# G208B.net
KiCad netlist of a schematic drawn in EAGLE
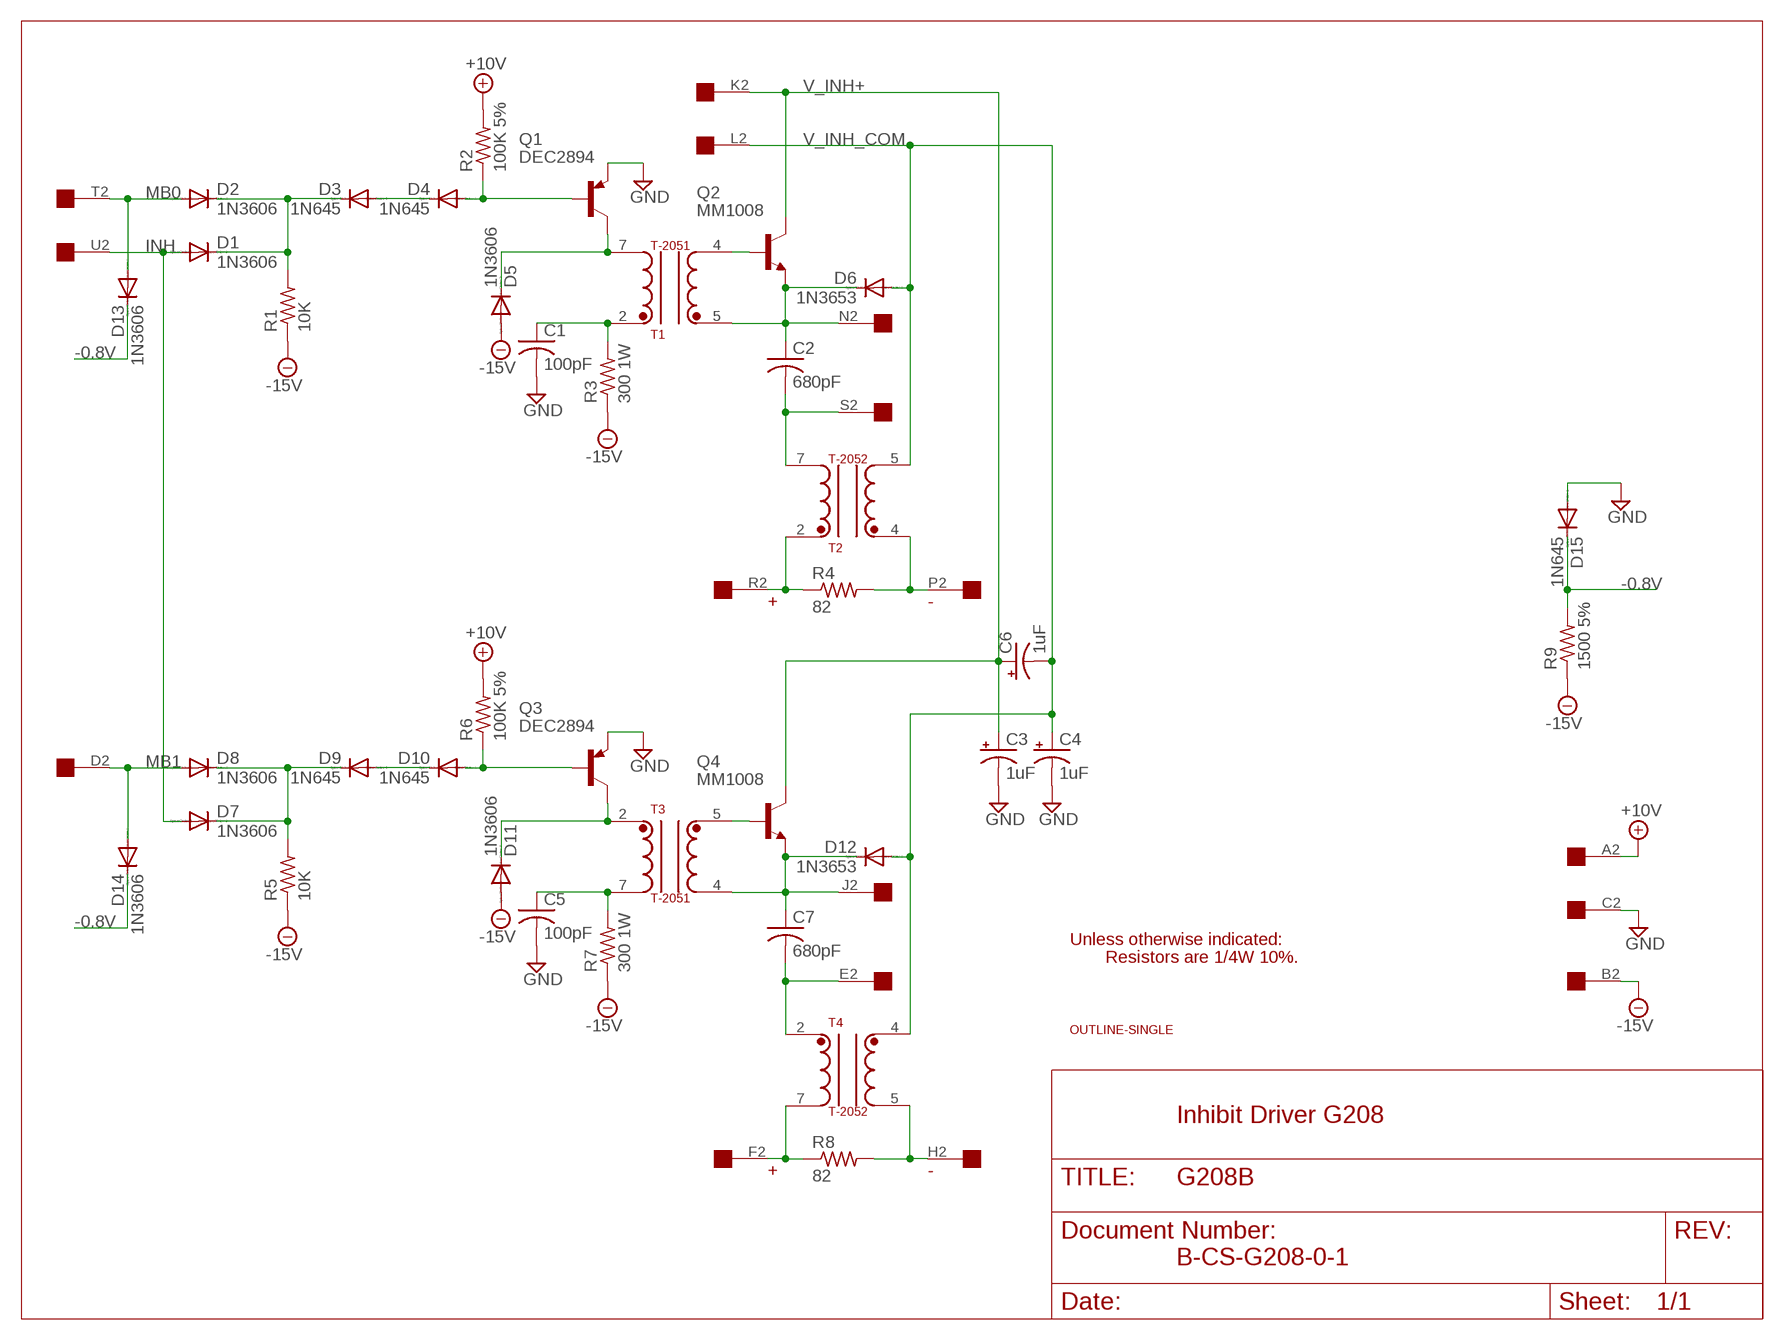
[diagram p0: schematic, sheet 1]

(export (version "E")
  (design (tool "Eeschema 10.0.6"))
  (components
    (comp (ref "C1")
      (value "100pF")
      (footprint "eagle-import:C075-032X103")
      (libsource (lib "eagle-import") (part "C-US075-032X103"))
    )
    (comp (ref "C2")
      (value "680pF")
      (footprint "eagle-import:C075-032X103")
      (libsource (lib "eagle-import") (part "C-US075-032X103"))
    )
    (comp (ref "C3")
      (value "1uF")
      (footprint "eagle-import:E25-9")
      (libsource (lib "eagle-import") (part "CPOL-USE25-9AXIAL"))
    )
    (comp (ref "C4")
      (value "1uF")
      (footprint "eagle-import:E25-9")
      (libsource (lib "eagle-import") (part "CPOL-USE25-9AXIAL"))
    )
    (comp (ref "C5")
      (value "100pF")
      (footprint "eagle-import:C075-032X103")
      (libsource (lib "eagle-import") (part "C-US075-032X103"))
    )
    (comp (ref "C6")
      (value "1uF")
      (footprint "eagle-import:E25-9")
      (libsource (lib "eagle-import") (part "CPOL-USE25-9AXIAL"))
    )
    (comp (ref "C7")
      (value "680pF")
      (footprint "eagle-import:C075-032X103")
      (libsource (lib "eagle-import") (part "C-US075-032X103"))
    )
    (comp (ref "D1")
      (value "1N3606")
      (footprint "eagle-import:DO35-10")
      (libsource (lib "eagle-import") (part "1N4148DO35-10"))
    )
    (comp (ref "D2")
      (value "1N3606")
      (footprint "eagle-import:DO35-10")
      (libsource (lib "eagle-import") (part "1N4148DO35-10"))
    )
    (comp (ref "D3")
      (value "1N645")
      (footprint "eagle-import:DO35-10")
      (libsource (lib "eagle-import") (part "1N4148DO35-10"))
    )
    (comp (ref "D4")
      (value "1N645")
      (footprint "eagle-import:DO35-10")
      (libsource (lib "eagle-import") (part "1N4148DO35-10"))
    )
    (comp (ref "D5")
      (value "1N3606")
      (footprint "eagle-import:DO35-10")
      (libsource (lib "eagle-import") (part "1N4148DO35-10"))
    )
    (comp (ref "D6")
      (value "1N3653")
      (footprint "eagle-import:DO35-10")
      (libsource (lib "eagle-import") (part "1N4148DO35-10"))
    )
    (comp (ref "D7")
      (value "1N3606")
      (footprint "eagle-import:DO35-10")
      (libsource (lib "eagle-import") (part "1N4148DO35-10"))
    )
    (comp (ref "D8")
      (value "1N3606")
      (footprint "eagle-import:DO35-10")
      (libsource (lib "eagle-import") (part "1N4148DO35-10"))
    )
    (comp (ref "D9")
      (value "1N645")
      (footprint "eagle-import:DO35-10")
      (libsource (lib "eagle-import") (part "1N4148DO35-10"))
    )
    (comp (ref "D10")
      (value "1N645")
      (footprint "eagle-import:DO35-10")
      (libsource (lib "eagle-import") (part "1N4148DO35-10"))
    )
    (comp (ref "D11")
      (value "1N3606")
      (footprint "eagle-import:DO35-10")
      (libsource (lib "eagle-import") (part "1N4148DO35-10"))
    )
    (comp (ref "D12")
      (value "1N3653")
      (footprint "eagle-import:DO35-10")
      (libsource (lib "eagle-import") (part "1N4148DO35-10"))
    )
    (comp (ref "D13")
      (value "1N3606")
      (footprint "eagle-import:DO35-10")
      (libsource (lib "eagle-import") (part "1N4148DO35-10"))
    )
    (comp (ref "D14")
      (value "1N3606")
      (footprint "eagle-import:DO35-10")
      (libsource (lib "eagle-import") (part "1N4148DO35-10"))
    )
    (comp (ref "D15")
      (value "1N645")
      (footprint "eagle-import:DO35-10")
      (libsource (lib "eagle-import") (part "1N4148DO35-10"))
    )
    (comp (ref "Q1")
      (value "DEC2894")
      (footprint "eagle-import:TO39")
      (libsource (lib "eagle-import") (part "2N2904"))
    )
    (comp (ref "Q2")
      (value "MM1008")
      (footprint "eagle-import:TO5")
      (libsource (lib "eagle-import") (part "2N2102"))
    )
    (comp (ref "Q3")
      (value "DEC2894")
      (footprint "eagle-import:TO39")
      (libsource (lib "eagle-import") (part "2N2904"))
    )
    (comp (ref "Q4")
      (value "MM1008")
      (footprint "eagle-import:TO5")
      (libsource (lib "eagle-import") (part "2N2102"))
    )
    (comp (ref "R1")
      (value "10K")
      (footprint "eagle-import:0207_10")
      (libsource (lib "eagle-import") (part "R-US_0207/10"))
    )
    (comp (ref "R2")
      (value "100K 5%")
      (footprint "eagle-import:0207_10")
      (libsource (lib "eagle-import") (part "R-US_0207/10"))
    )
    (comp (ref "R3")
      (value "300 1W")
      (footprint "eagle-import:0617_22")
      (libsource (lib "eagle-import") (part "R-US_0617/22"))
    )
    (comp (ref "R4")
      (value "82")
      (footprint "eagle-import:0207_10")
      (libsource (lib "eagle-import") (part "R-US_0207/10"))
    )
    (comp (ref "R5")
      (value "10K")
      (footprint "eagle-import:0207_10")
      (libsource (lib "eagle-import") (part "R-US_0207/10"))
    )
    (comp (ref "R6")
      (value "100K 5%")
      (footprint "eagle-import:0207_10")
      (libsource (lib "eagle-import") (part "R-US_0207/10"))
    )
    (comp (ref "R7")
      (value "300 1W")
      (footprint "eagle-import:0617_22")
      (libsource (lib "eagle-import") (part "R-US_0617/22"))
    )
    (comp (ref "R8")
      (value "82")
      (footprint "eagle-import:0207_10")
      (libsource (lib "eagle-import") (part "R-US_0207/10"))
    )
    (comp (ref "R9")
      (value "1500 5%")
      (footprint "eagle-import:0207_10")
      (libsource (lib "eagle-import") (part "R-US_0207/10"))
    )
    (comp (ref "T1")
      (value "T-2051")
      (footprint "eagle-import:TRANSFORMER")
      (libsource (lib "eagle-import") (part "T-2051"))
    )
    (comp (ref "T2")
      (value "T-2052")
      (footprint "eagle-import:TRANSFORMER")
      (libsource (lib "eagle-import") (part "T-2052"))
    )
    (comp (ref "T3")
      (value "T-2051")
      (footprint "eagle-import:TRANSFORMER")
      (libsource (lib "eagle-import") (part "T-2051"))
    )
    (comp (ref "T4")
      (value "T-2052")
      (footprint "eagle-import:TRANSFORMER")
      (libsource (lib "eagle-import") (part "T-2052"))
    )
    (comp (ref "U$1")
      (value "OUTLINE-SINGLE")
      (footprint "eagle-import:SINGLE")
      (libsource (lib "eagle-import") (part "OUTLINE-SINGLE"))
    )
    (comp (ref "U$2")
      (value "EDGE-1")
      (footprint "eagle-import:EDGE-CON1")
      (libsource (lib "eagle-import") (part "EDGE-1"))
    )
  )
  (nets
    (net (code "1") (name "+10V") (class "Default")
      (node (ref "R2") (pin "2") (pinfunction "2_2") (pintype "passive"))
      (node (ref "R6") (pin "2") (pinfunction "2_2") (pintype "passive"))
      (node (ref "U$2") (pin "A2") (pinfunction "1_A2") (pintype "bidirectional"))
    )
    (net (code "2") (name "-15V") (class "Default")
      (node (ref "D11") (pin "A") (pinfunction "A_A") (pintype "passive"))
      (node (ref "D5") (pin "A") (pinfunction "A_A") (pintype "passive"))
      (node (ref "R1") (pin "1") (pinfunction "1_1") (pintype "passive"))
      (node (ref "R3") (pin "1") (pinfunction "1_1") (pintype "passive"))
      (node (ref "R5") (pin "1") (pinfunction "1_1") (pintype "passive"))
      (node (ref "R7") (pin "1") (pinfunction "1_1") (pintype "passive"))
      (node (ref "R9") (pin "1") (pinfunction "1_1") (pintype "passive"))
      (node (ref "U$2") (pin "B2") (pinfunction "1_B2") (pintype "bidirectional"))
    )
    (net (code "3") (name "/-0.8V") (class "Default")
      (node (ref "D13") (pin "C") (pinfunction "C_C") (pintype "passive"))
      (node (ref "D14") (pin "C") (pinfunction "C_C") (pintype "passive"))
      (node (ref "D15") (pin "C") (pinfunction "C_C") (pintype "passive"))
      (node (ref "R9") (pin "2") (pinfunction "2_2") (pintype "passive"))
    )
    (net (code "4") (name "/INH") (class "Default")
      (node (ref "D1") (pin "A") (pinfunction "A_A") (pintype "passive"))
      (node (ref "D7") (pin "A") (pinfunction "A_A") (pintype "passive"))
      (node (ref "U$2") (pin "U2") (pinfunction "1_U2") (pintype "bidirectional"))
    )
    (net (code "5") (name "/MB0") (class "Default")
      (node (ref "D13") (pin "A") (pinfunction "A_A") (pintype "passive"))
      (node (ref "D2") (pin "A") (pinfunction "A_A") (pintype "passive"))
      (node (ref "U$2") (pin "T2") (pinfunction "1_T2") (pintype "bidirectional"))
    )
    (net (code "6") (name "/MB1") (class "Default")
      (node (ref "D14") (pin "A") (pinfunction "A_A") (pintype "passive"))
      (node (ref "D8") (pin "A") (pinfunction "A_A") (pintype "passive"))
      (node (ref "U$2") (pin "D2") (pinfunction "1_D2") (pintype "bidirectional"))
    )
    (net (code "7") (name "/V_INH+") (class "Default")
      (node (ref "C3") (pin "+") (pinfunction "+_+") (pintype "passive"))
      (node (ref "C6") (pin "+") (pinfunction "+_+") (pintype "passive"))
      (node (ref "Q2") (pin "3") (pinfunction "C_3") (pintype "passive"))
      (node (ref "Q4") (pin "3") (pinfunction "C_3") (pintype "passive"))
      (node (ref "U$2") (pin "K2") (pinfunction "1_K2") (pintype "bidirectional"))
    )
    (net (code "8") (name "/V_INH_COM") (class "Default")
      (node (ref "C4") (pin "+") (pinfunction "+_+") (pintype "passive"))
      (node (ref "C6") (pin "-") (pinfunction "-_-") (pintype "passive"))
      (node (ref "D12") (pin "A") (pinfunction "A_A") (pintype "passive"))
      (node (ref "D6") (pin "A") (pinfunction "A_A") (pintype "passive"))
      (node (ref "T2") (pin "5") (pinfunction "P$5_5") (pintype "passive"))
      (node (ref "T4") (pin "4") (pinfunction "P$4_4") (pintype "passive"))
      (node (ref "U$2") (pin "L2") (pinfunction "1_L2") (pintype "bidirectional"))
    )
    (net (code "9") (name "GND") (class "Default")
      (node (ref "C1") (pin "2") (pinfunction "2_2") (pintype "passive"))
      (node (ref "C3") (pin "-") (pinfunction "-_-") (pintype "passive"))
      (node (ref "C4") (pin "-") (pinfunction "-_-") (pintype "passive"))
      (node (ref "C5") (pin "2") (pinfunction "2_2") (pintype "passive"))
      (node (ref "D15") (pin "A") (pinfunction "A_A") (pintype "passive"))
      (node (ref "Q1") (pin "1") (pinfunction "E_1") (pintype "passive"))
      (node (ref "Q3") (pin "1") (pinfunction "E_1") (pintype "passive"))
      (node (ref "U$2") (pin "C2") (pinfunction "1_C2") (pintype "bidirectional"))
    )
    (net (code "10") (name "Net-(D1-PadC)") (class "Default")
      (node (ref "D1") (pin "C") (pinfunction "C_C") (pintype "passive"))
      (node (ref "D2") (pin "C") (pinfunction "C_C") (pintype "passive"))
      (node (ref "D3") (pin "C") (pinfunction "C_C") (pintype "passive"))
      (node (ref "R1") (pin "2") (pinfunction "2_2") (pintype "passive"))
    )
    (net (code "11") (name "Net-(D3-PadA)") (class "Default")
      (node (ref "D3") (pin "A") (pinfunction "A_A") (pintype "passive"))
      (node (ref "D4") (pin "C") (pinfunction "C_C") (pintype "passive"))
    )
    (net (code "12") (name "Net-(D7-PadC)") (class "Default")
      (node (ref "D7") (pin "C") (pinfunction "C_C") (pintype "passive"))
      (node (ref "D8") (pin "C") (pinfunction "C_C") (pintype "passive"))
      (node (ref "D9") (pin "C") (pinfunction "C_C") (pintype "passive"))
      (node (ref "R5") (pin "2") (pinfunction "2_2") (pintype "passive"))
    )
    (net (code "13") (name "Net-(D10-PadC)") (class "Default")
      (node (ref "D10") (pin "C") (pinfunction "C_C") (pintype "passive"))
      (node (ref "D9") (pin "A") (pinfunction "A_A") (pintype "passive"))
    )
    (net (code "14") (name "Net-(Q1-B)") (class "Default")
      (node (ref "D4") (pin "A") (pinfunction "A_A") (pintype "passive"))
      (node (ref "Q1") (pin "2") (pinfunction "B_2") (pintype "passive"))
      (node (ref "R2") (pin "1") (pinfunction "1_1") (pintype "passive"))
    )
    (net (code "15") (name "Net-(Q1-C)") (class "Default")
      (node (ref "D5") (pin "C") (pinfunction "C_C") (pintype "passive"))
      (node (ref "Q1") (pin "3") (pinfunction "C_3") (pintype "passive"))
      (node (ref "T1") (pin "7") (pinfunction "P$7_7") (pintype "passive"))
    )
    (net (code "16") (name "Net-(Q2-B)") (class "Default")
      (node (ref "Q2") (pin "2") (pinfunction "B_2") (pintype "passive"))
      (node (ref "T1") (pin "4") (pinfunction "P$5_4") (pintype "passive"))
    )
    (net (code "17") (name "Net-(Q2-E)") (class "Default")
      (node (ref "C2") (pin "1") (pinfunction "1_1") (pintype "passive"))
      (node (ref "D6") (pin "C") (pinfunction "C_C") (pintype "passive"))
      (node (ref "Q2") (pin "1") (pinfunction "E_1") (pintype "passive"))
      (node (ref "T1") (pin "5") (pinfunction "P$4_5") (pintype "passive"))
      (node (ref "U$2") (pin "N2") (pinfunction "1_N2") (pintype "bidirectional"))
    )
    (net (code "18") (name "Net-(Q3-B)") (class "Default")
      (node (ref "D10") (pin "A") (pinfunction "A_A") (pintype "passive"))
      (node (ref "Q3") (pin "2") (pinfunction "B_2") (pintype "passive"))
      (node (ref "R6") (pin "1") (pinfunction "1_1") (pintype "passive"))
    )
    (net (code "19") (name "Net-(Q3-C)") (class "Default")
      (node (ref "D11") (pin "C") (pinfunction "C_C") (pintype "passive"))
      (node (ref "Q3") (pin "3") (pinfunction "C_3") (pintype "passive"))
      (node (ref "T3") (pin "2") (pinfunction "P$2_2") (pintype "passive"))
    )
    (net (code "20") (name "Net-(Q4-B)") (class "Default")
      (node (ref "Q4") (pin "2") (pinfunction "B_2") (pintype "passive"))
      (node (ref "T3") (pin "5") (pinfunction "P$4_5") (pintype "passive"))
    )
    (net (code "21") (name "Net-(Q4-E)") (class "Default")
      (node (ref "C7") (pin "1") (pinfunction "1_1") (pintype "passive"))
      (node (ref "D12") (pin "C") (pinfunction "C_C") (pintype "passive"))
      (node (ref "Q4") (pin "1") (pinfunction "E_1") (pintype "passive"))
      (node (ref "T3") (pin "4") (pinfunction "P$5_4") (pintype "passive"))
      (node (ref "U$2") (pin "J2") (pinfunction "1_J2") (pintype "bidirectional"))
    )
    (net (code "22") (name "Net-(T1-P$2)") (class "Default")
      (node (ref "C1") (pin "1") (pinfunction "1_1") (pintype "passive"))
      (node (ref "R3") (pin "2") (pinfunction "2_2") (pintype "passive"))
      (node (ref "T1") (pin "2") (pinfunction "P$2_2") (pintype "passive"))
    )
    (net (code "23") (name "Net-(T2-P$2)") (class "Default")
      (node (ref "R4") (pin "1") (pinfunction "1_1") (pintype "passive"))
      (node (ref "T2") (pin "2") (pinfunction "P$2_2") (pintype "passive"))
      (node (ref "U$2") (pin "R2") (pinfunction "1_R2") (pintype "bidirectional"))
    )
    (net (code "24") (name "Net-(T2-P$4)") (class "Default")
      (node (ref "R4") (pin "2") (pinfunction "2_2") (pintype "passive"))
      (node (ref "T2") (pin "4") (pinfunction "P$4_4") (pintype "passive"))
      (node (ref "U$2") (pin "P2") (pinfunction "1_P2") (pintype "bidirectional"))
    )
    (net (code "25") (name "Net-(T2-P$7)") (class "Default")
      (node (ref "C2") (pin "2") (pinfunction "2_2") (pintype "passive"))
      (node (ref "T2") (pin "7") (pinfunction "P$7_7") (pintype "passive"))
      (node (ref "U$2") (pin "S2") (pinfunction "1_S2") (pintype "bidirectional"))
    )
    (net (code "26") (name "Net-(T3-P$7)") (class "Default")
      (node (ref "C5") (pin "1") (pinfunction "1_1") (pintype "passive"))
      (node (ref "R7") (pin "2") (pinfunction "2_2") (pintype "passive"))
      (node (ref "T3") (pin "7") (pinfunction "P$7_7") (pintype "passive"))
    )
    (net (code "27") (name "Net-(T4-P$2)") (class "Default")
      (node (ref "C7") (pin "2") (pinfunction "2_2") (pintype "passive"))
      (node (ref "T4") (pin "2") (pinfunction "P$2_2") (pintype "passive"))
      (node (ref "U$2") (pin "E2") (pinfunction "1_E2") (pintype "bidirectional"))
    )
    (net (code "28") (name "Net-(T4-P$5)") (class "Default")
      (node (ref "R8") (pin "2") (pinfunction "2_2") (pintype "passive"))
      (node (ref "T4") (pin "5") (pinfunction "P$5_5") (pintype "passive"))
      (node (ref "U$2") (pin "H2") (pinfunction "1_H2") (pintype "bidirectional"))
    )
    (net (code "29") (name "Net-(T4-P$7)") (class "Default")
      (node (ref "R8") (pin "1") (pinfunction "1_1") (pintype "passive"))
      (node (ref "T4") (pin "7") (pinfunction "P$7_7") (pintype "passive"))
      (node (ref "U$2") (pin "F2") (pinfunction "1_F2") (pintype "bidirectional"))
    )
  )
)
